# first.net
KiCad netlist of a schematic drawn in EasyEDA
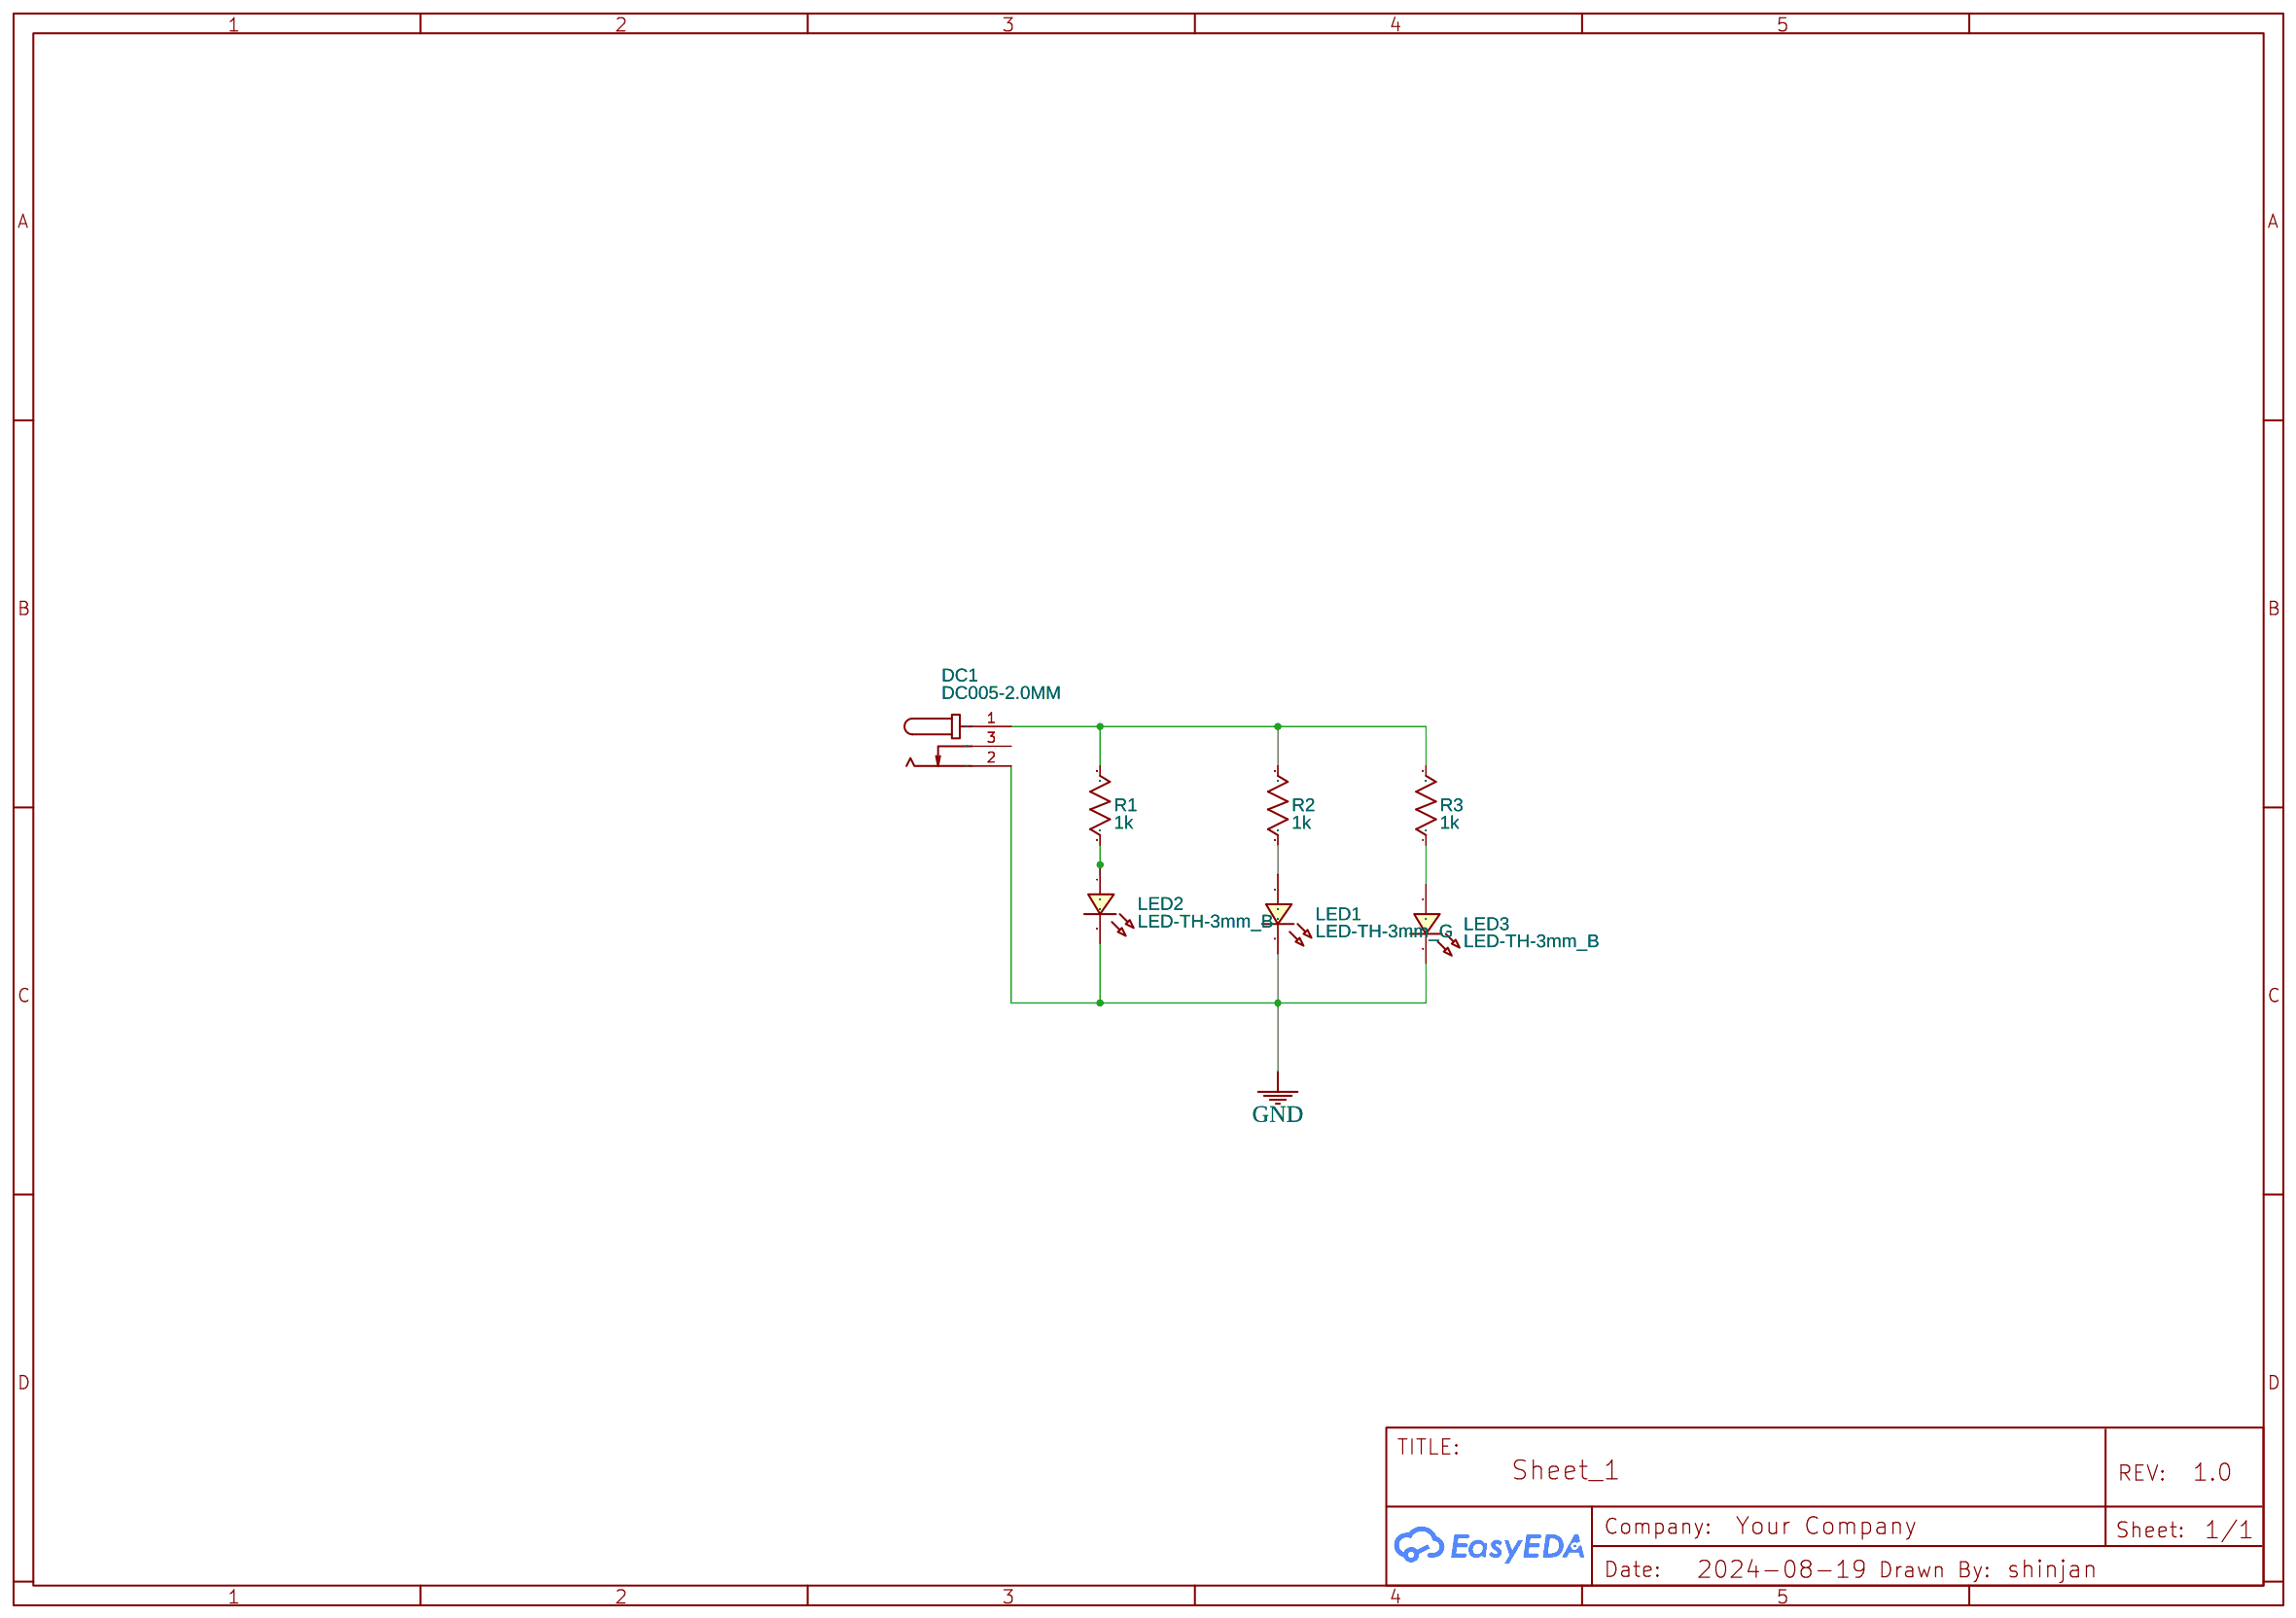
[diagram p0: schematic sheet]

(export (version "E")
  (design (tool "Eeschema 10.0.6"))
  (components
    (comp (ref "DC1")
      (value "DC005-2.0MM")
      (fields (field (name "Manufacturer") "SOFNG"))
      (libsource (lib "") (part "DC005-2.0MM"))
    )
    (comp (ref "LED1")
      (value "LED-TH-3mm_G")
      (fields
        (field (name "Manufacturer Part") "204-10SYGD/S530-E3")
        (field (name "Manufacturer") "EVERLIGHT(台湾亿光)")
      )
      (libsource (lib "") (part "LED-TH-3mm_G"))
    )
    (comp (ref "LED2")
      (value "LED-TH-3mm_B")
      (fields
        (field (name "Manufacturer Part") "204-10SUBC/S400-A4")
        (field (name "Manufacturer") "EVERLIGHT(台湾亿光)")
      )
      (libsource (lib "") (part "LED-TH-3mm_B"))
    )
    (comp (ref "LED3")
      (value "LED-TH-3mm_B")
      (fields
        (field (name "Manufacturer Part") "204-10SUBC/S400-A4")
        (field (name "Manufacturer") "EVERLIGHT(台湾亿光)")
      )
      (libsource (lib "") (part "LED-TH-3mm_B"))
    )
    (comp (ref "R1")
      (value "1k")
      (fields (field (name "Manufacturer Part") "MFR-25FRF52-130R") (field (name "Manufacturer") "YAGEO(国巨)"))
      (libsource (lib "") (part "R_0603_US"))
    )
    (comp (ref "R2")
      (value "1k")
      (fields (field (name "Manufacturer Part") "MFR-25FRF52-130R") (field (name "Manufacturer") "YAGEO(国巨)"))
      (libsource (lib "") (part "R_0603_US"))
    )
    (comp (ref "R3")
      (value "1k")
      (fields (field (name "Manufacturer Part") "MFR-25FRF52-130R") (field (name "Manufacturer") "YAGEO(国巨)"))
      (libsource (lib "") (part "R_0603_US"))
    )
  )
  (nets
    (net (code "1") (name "GND") (class "Default")
      (node (ref "DC1") (pin "2") (pinfunction "2_2") (pintype "unspecified"))
      (node (ref "LED1") (pin "2") (pinfunction "2_2") (pintype "unspecified"))
      (node (ref "LED2") (pin "2") (pinfunction "2_2") (pintype "unspecified"))
      (node (ref "LED3") (pin "2") (pinfunction "2_2") (pintype "unspecified"))
    )
    (net (code "2") (name "Net-(DC1-Pad1)") (class "Default")
      (node (ref "DC1") (pin "1") (pinfunction "1_1") (pintype "unspecified"))
      (node (ref "R1") (pin "2") (pinfunction "2_2") (pintype "unspecified"))
      (node (ref "R2") (pin "2") (pinfunction "2_2") (pintype "unspecified"))
      (node (ref "R3") (pin "2") (pinfunction "2_2") (pintype "unspecified"))
    )
    (net (code "3") (name "Net-(LED1-Pad1)") (class "Default")
      (node (ref "LED1") (pin "1") (pinfunction "1_1") (pintype "unspecified"))
      (node (ref "R2") (pin "1") (pinfunction "1_1") (pintype "unspecified"))
    )
    (net (code "4") (name "Net-(LED2-Pad1)") (class "Default")
      (node (ref "LED2") (pin "1") (pinfunction "1_1") (pintype "unspecified"))
      (node (ref "R1") (pin "1") (pinfunction "1_1") (pintype "unspecified"))
    )
    (net (code "5") (name "Net-(LED3-Pad1)") (class "Default")
      (node (ref "LED3") (pin "1") (pinfunction "1_1") (pintype "unspecified"))
      (node (ref "R3") (pin "1") (pinfunction "1_1") (pintype "unspecified"))
    )
    (net (code "6") (name "unconnected-(DC1-Pad3)") (class "Default")
      (node (ref "DC1") (pin "3") (pinfunction "3_3") (pintype "unspecified"))
    )
  )
)
